# keyboard_main.net
KiCad netlist of a schematic drawn in Altium Designer
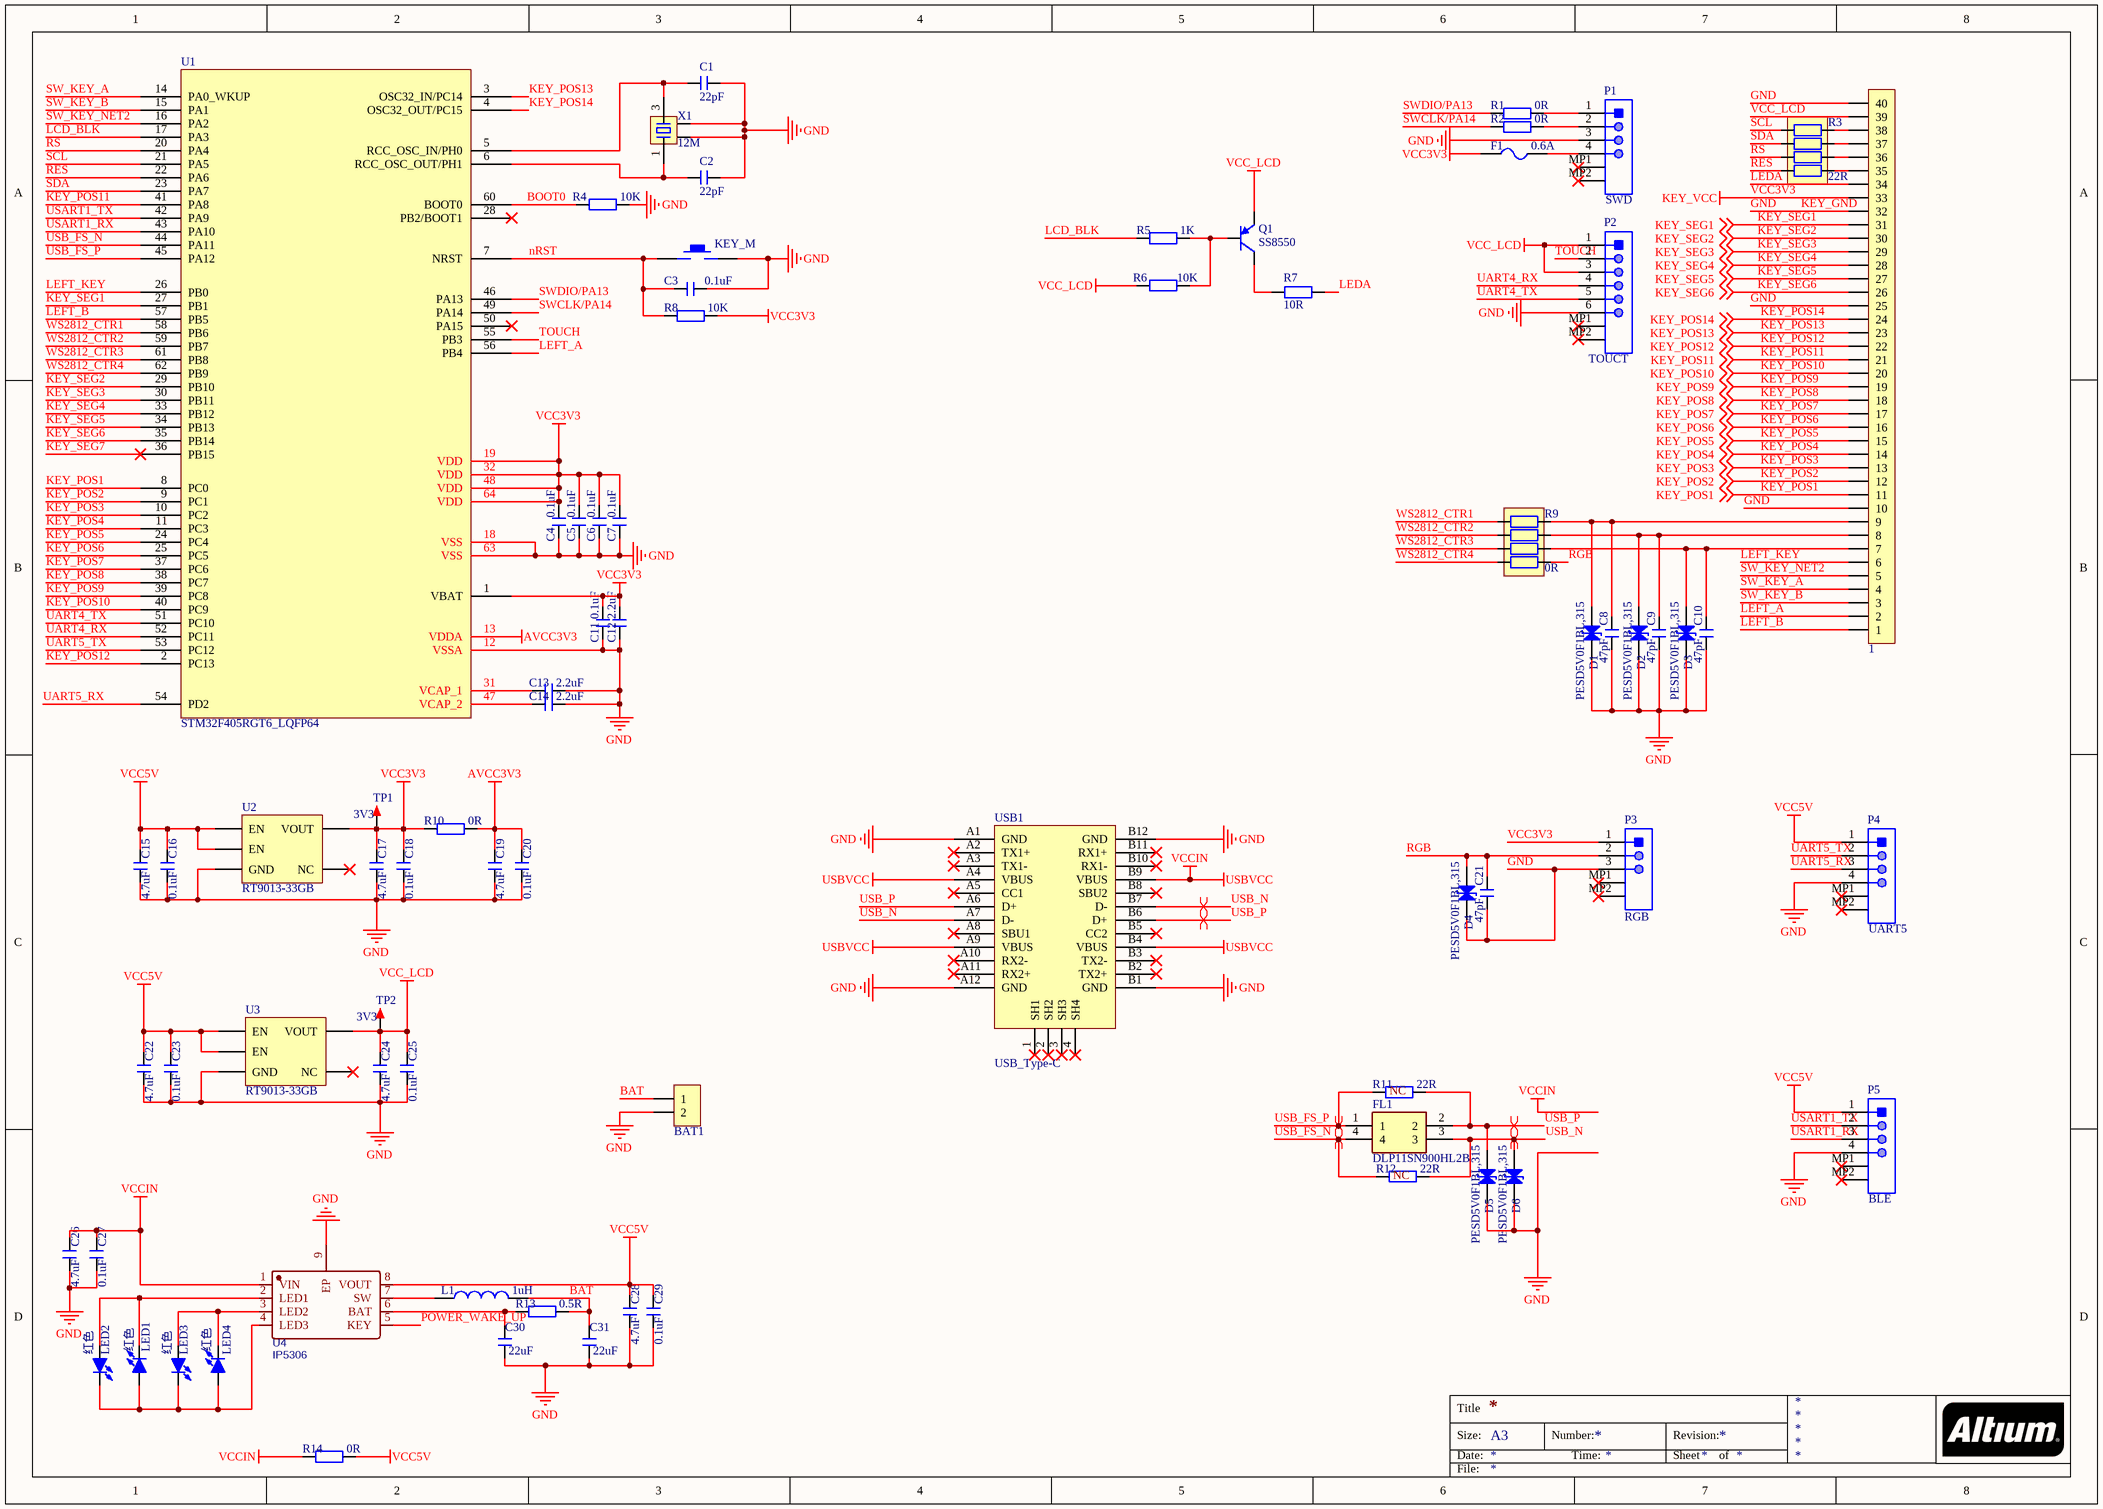
[diagram p0: keyboard_main.SchDoc]

(export (version "E")
  (design (tool "Eeschema 10.0.6"))
  (components
    (comp (ref "1")
      (value "FPC1.0-40P")
      (footprint "FPC0.5 2H-WS-40P")
      (description "FPC连接器")
      (fields (field (name "版权归属") "黎明电子style"))
      (libsource (lib "FPC连接器") (part "FPC-40P"))
    )
    (comp (ref "BAT1")
      (value "HDR-1X2")
      (footprint "XH2.54-WI-2P")
      (description "2P接插件")
      (libsource (lib "5.3 - 接插件-脚距2.54 (100mil) ") (part "Header 2"))
    )
    (comp (ref "C1")
      (value "22pF")
      (footprint "C 0402_L")
      (description "贴片电容")
      (libsource (lib "0.1 - 电阻-电容-电感") (part "C"))
    )
    (comp (ref "C2")
      (value "22pF")
      (footprint "C 0402_L")
      (description "贴片电容")
      (libsource (lib "0.1 - 电阻-电容-电感") (part "C"))
    )
    (comp (ref "C3")
      (value "0.1uF")
      (footprint "C 0402_L")
      (description "贴片电容")
      (libsource (lib "0.1 - 电阻-电容-电感") (part "C"))
    )
    (comp (ref "C4")
      (value "0.1uF")
      (footprint "C 0402_L")
      (description "贴片电容")
      (libsource (lib "0.1 - 电阻-电容-电感") (part "C"))
    )
    (comp (ref "C5")
      (value "0.1uF")
      (footprint "C 0402_L")
      (description "贴片电容")
      (libsource (lib "0.1 - 电阻-电容-电感") (part "C"))
    )
    (comp (ref "C6")
      (value "0.1uF")
      (footprint "C 0402_L")
      (description "贴片电容")
      (libsource (lib "0.1 - 电阻-电容-电感") (part "C"))
    )
    (comp (ref "C7")
      (value "0.1uF")
      (footprint "C 0402_L")
      (description "贴片电容")
      (libsource (lib "0.1 - 电阻-电容-电感") (part "C"))
    )
    (comp (ref "C8")
      (value "47pF")
      (footprint "C 0402_L")
      (description "贴片电容")
      (libsource (lib "0.1 - 电阻-电容-电感") (part "C"))
    )
    (comp (ref "C9")
      (value "47pF")
      (footprint "C 0402_L")
      (description "贴片电容")
      (libsource (lib "0.1 - 电阻-电容-电感") (part "C"))
    )
    (comp (ref "C10")
      (value "47pF")
      (footprint "C 0402_L")
      (description "贴片电容")
      (libsource (lib "0.1 - 电阻-电容-电感") (part "C"))
    )
    (comp (ref "C11")
      (value "0.1uF")
      (footprint "C 0402_L")
      (description "贴片电容")
      (libsource (lib "0.1 - 电阻-电容-电感") (part "C"))
    )
    (comp (ref "C12")
      (value "2.2uF")
      (footprint "C 0402_L")
      (description "贴片电容")
      (libsource (lib "0.1 - 电阻-电容-电感") (part "C"))
    )
    (comp (ref "C13")
      (value "2.2uF")
      (footprint "C 0402_L")
      (description "贴片电容")
      (libsource (lib "0.1 - 电阻-电容-电感") (part "C"))
    )
    (comp (ref "C14")
      (value "2.2uF")
      (footprint "C 0402_L")
      (description "贴片电容")
      (libsource (lib "0.1 - 电阻-电容-电感") (part "C"))
    )
    (comp (ref "C15")
      (value "4.7uF")
      (footprint "C 0402_L")
      (description "贴片电容")
      (libsource (lib "0.1 - 电阻-电容-电感") (part "C"))
    )
    (comp (ref "C16")
      (value "0.1uF")
      (footprint "C 0402_L")
      (description "贴片电容")
      (libsource (lib "0.1 - 电阻-电容-电感") (part "C"))
    )
    (comp (ref "C17")
      (value "4.7uF")
      (footprint "C 0402_L")
      (description "贴片电容")
      (libsource (lib "0.1 - 电阻-电容-电感") (part "C"))
    )
    (comp (ref "C18")
      (value "0.1uF")
      (footprint "C 0402_L")
      (description "贴片电容")
      (libsource (lib "0.1 - 电阻-电容-电感") (part "C"))
    )
    (comp (ref "C19")
      (value "4.7uF")
      (footprint "C 0402_L")
      (description "贴片电容")
      (libsource (lib "0.1 - 电阻-电容-电感") (part "C"))
    )
    (comp (ref "C20")
      (value "0.1uF")
      (footprint "C 0402_L")
      (description "贴片电容")
      (libsource (lib "0.1 - 电阻-电容-电感") (part "C"))
    )
    (comp (ref "C21")
      (value "47pF")
      (footprint "C 0402_L")
      (description "贴片电容")
      (libsource (lib "0.1 - 电阻-电容-电感") (part "C"))
    )
    (comp (ref "C22")
      (value "4.7uF")
      (footprint "C 0402_L")
      (description "贴片电容")
      (libsource (lib "0.1 - 电阻-电容-电感") (part "C"))
    )
    (comp (ref "C23")
      (value "0.1uF")
      (footprint "C 0402_L")
      (description "贴片电容")
      (libsource (lib "0.1 - 电阻-电容-电感") (part "C"))
    )
    (comp (ref "C24")
      (value "4.7uF")
      (footprint "C 0402_L")
      (description "贴片电容")
      (libsource (lib "0.1 - 电阻-电容-电感") (part "C"))
    )
    (comp (ref "C25")
      (value "0.1uF")
      (footprint "C 0402_L")
      (description "贴片电容")
      (libsource (lib "0.1 - 电阻-电容-电感") (part "C"))
    )
    (comp (ref "C26")
      (value "4.7uF")
      (footprint "C 0402_L")
      (description "贴片电容")
      (libsource (lib "0.1 - 电阻-电容-电感") (part "C"))
    )
    (comp (ref "C27")
      (value "0.1uF")
      (footprint "C 0402_L")
      (description "贴片电容")
      (libsource (lib "0.1 - 电阻-电容-电感") (part "C"))
    )
    (comp (ref "C28")
      (value "4.7uF")
      (footprint "C 0402_L")
      (description "贴片电容")
      (libsource (lib "0.1 - 电阻-电容-电感") (part "C"))
    )
    (comp (ref "C29")
      (value "0.1uF")
      (footprint "C 0402_L")
      (description "贴片电容")
      (libsource (lib "0.1 - 电阻-电容-电感") (part "C"))
    )
    (comp (ref "C30")
      (value "22uF")
      (footprint "C 0603_L")
      (description "贴片电容")
      (libsource (lib "0.1 - 电阻-电容-电感") (part "C"))
    )
    (comp (ref "C31")
      (value "22uF")
      (footprint "C 0603_L")
      (description "贴片电容")
      (libsource (lib "0.1 - 电阻-电容-电感") (part "C"))
    )
    (comp (ref "D1")
      (value "PESD5V0F1BL,315")
      (footprint "SOD-882_L1.0-W0.6-BI")
      (description "PESD5V0F1BL,315、ESD二极管、5.5V")
      (libsource (lib "0.2 -  二极管-整流桥") (part "PESD5V0F1BL,315"))
    )
    (comp (ref "D2")
      (value "PESD5V0F1BL,315")
      (footprint "SOD-882_L1.0-W0.6-BI")
      (description "PESD5V0F1BL,315、ESD二极管、5.5V")
      (libsource (lib "0.2 -  二极管-整流桥") (part "PESD5V0F1BL,315"))
    )
    (comp (ref "D3")
      (value "PESD5V0F1BL,315")
      (footprint "SOD-882_L1.0-W0.6-BI")
      (description "PESD5V0F1BL,315、ESD二极管、5.5V")
      (libsource (lib "0.2 -  二极管-整流桥") (part "PESD5V0F1BL,315"))
    )
    (comp (ref "D4")
      (value "PESD5V0F1BL,315")
      (footprint "SOD-882_L1.0-W0.6-BI")
      (description "PESD5V0F1BL,315、ESD二极管、5.5V")
      (libsource (lib "0.2 -  二极管-整流桥") (part "PESD5V0F1BL,315"))
    )
    (comp (ref "D5")
      (value "PESD5V0F1BL,315")
      (footprint "SOD-882_L1.0-W0.6-BI")
      (description "PESD5V0F1BL,315、ESD二极管、5.5V")
      (libsource (lib "0.2 -  二极管-整流桥") (part "PESD5V0F1BL,315"))
    )
    (comp (ref "D6")
      (value "PESD5V0F1BL,315")
      (footprint "SOD-882_L1.0-W0.6-BI")
      (description "PESD5V0F1BL,315、ESD二极管、5.5V")
      (libsource (lib "0.2 -  二极管-整流桥") (part "PESD5V0F1BL,315"))
    )
    (comp (ref "F1")
      (value "0.6A")
      (footprint "FU 0402")
      (description "贴片保险丝")
      (libsource (lib "2.0 - 保险丝-晶振-光耦") (part "FU"))
    )
    (comp (ref "FL1")
      (value "DLP11SN900HL2B")
      (footprint "vSeasky:DLP11SA350HL2B")
      (description "Filter")
      (fields (field (name "MOUSER PART NUMBER") "81-DLP11SN900HL2B"))
      (libsource (lib "vSeasky") (part "DLP11SN900HL2B"))
    )
    (comp (ref "L1")
      (value "1uH")
      (footprint "L 1812")
      (description "小功率贴片电感")
      (libsource (lib "0.1 - 电阻-电容-电感") (part "L"))
    )
    (comp (ref "LED1")
      (value "红色")
      (footprint "LED 0805G")
      (description "贴片LED")
      (libsource (lib "0.3 - LED发光二极管") (part "LED-SMD"))
    )
    (comp (ref "LED2")
      (value "红色")
      (footprint "LED 0805G")
      (description "贴片LED")
      (libsource (lib "0.3 - LED发光二极管") (part "LED-SMD"))
    )
    (comp (ref "LED3")
      (value "红色")
      (footprint "LED 0805G")
      (description "贴片LED")
      (libsource (lib "0.3 - LED发光二极管") (part "LED-SMD"))
    )
    (comp (ref "LED4")
      (value "红色")
      (footprint "LED 0805G")
      (description "贴片LED")
      (libsource (lib "0.3 - LED发光二极管") (part "LED-SMD"))
    )
    (comp (ref "P1")
      (value "SWD")
      (footprint "JST-SM04B-GHS-TB_V")
      (fields (field (name "MANUFACTURER") "JST"))
      (libsource (lib "JST GH connector") (part "SM04B-GHS-TB(LF)(SN)"))
    )
    (comp (ref "P2")
      (value "TOUCT")
      (footprint "JST-SM06B-GHS-TB_V")
      (fields (field (name "MANUFACTURER") "JST"))
      (libsource (lib "JST GH connector") (part "SM06B-GHS-TB(LF)(SN)"))
    )
    (comp (ref "P3")
      (value "RGB")
      (footprint "JST-SM03B-GHS-TB_V")
      (fields (field (name "MANUFACTURER") "JST"))
      (libsource (lib "JST GH connector") (part "SM03B-GHS-TB(LF)(SN)"))
    )
    (comp (ref "P4")
      (value "UART5")
      (footprint "JST-SM04B-GHS-TB_V")
      (fields (field (name "MANUFACTURER") "JST"))
      (libsource (lib "JST GH connector") (part "SM04B-GHS-TB(LF)(SN)"))
    )
    (comp (ref "P5")
      (value "BLE")
      (footprint "JST-SM04B-GHS-TB_V")
      (fields (field (name "MANUFACTURER") "JST"))
      (libsource (lib "JST GH connector") (part "SM04B-GHS-TB(LF)(SN)"))
    )
    (comp (ref "Q1")
      (value "SS8550")
      (footprint "SOT23-3N")
      (description "高频放大-PNP型")
      (libsource (lib "0.4 - 三极管") (part "8550-SMD"))
    )
    (comp (ref "R1")
      (value "0R")
      (footprint "R 0402_L")
      (description "贴片电阻")
      (libsource (lib "0.1 - 电阻-电容-电感") (part "R"))
    )
    (comp (ref "R2")
      (value "0R")
      (footprint "R 0402_L")
      (description "贴片电阻")
      (libsource (lib "0.1 - 电阻-电容-电感") (part "R"))
    )
    (comp (ref "R3")
      (value "22R")
      (footprint "RCA-8P4R-0402")
      (description "贴片排阻")
      (libsource (lib "0.1 - 电阻-电容-电感") (part "R-8P4R"))
    )
    (comp (ref "R4")
      (value "10K")
      (footprint "R 0402_L")
      (description "贴片电阻")
      (libsource (lib "0.1 - 电阻-电容-电感") (part "R"))
    )
    (comp (ref "R5")
      (value "1K")
      (footprint "R 0402_L")
      (description "贴片电阻")
      (libsource (lib "0.1 - 电阻-电容-电感") (part "R"))
    )
    (comp (ref "R6")
      (value "10K")
      (footprint "R 0402_L")
      (description "贴片电阻")
      (libsource (lib "0.1 - 电阻-电容-电感") (part "R"))
    )
    (comp (ref "R7")
      (value "10R")
      (footprint "R 0402_L")
      (description "贴片电阻")
      (libsource (lib "0.1 - 电阻-电容-电感") (part "R"))
    )
    (comp (ref "R8")
      (value "10K")
      (footprint "R 0402_L")
      (description "贴片电阻")
      (libsource (lib "0.1 - 电阻-电容-电感") (part "R"))
    )
    (comp (ref "R9")
      (value "0R")
      (footprint "RCA-8P4R-0402")
      (description "贴片排阻")
      (libsource (lib "0.1 - 电阻-电容-电感") (part "R-8P4R"))
    )
    (comp (ref "R10")
      (value "0R")
      (footprint "R 0402_L")
      (description "贴片电阻")
      (libsource (lib "0.1 - 电阻-电容-电感") (part "R"))
    )
    (comp (ref "R11")
      (value "22R")
      (footprint "R 0402_L")
      (description "贴片电阻")
      (libsource (lib "0.1 - 电阻-电容-电感") (part "R"))
    )
    (comp (ref "R12")
      (value "22R")
      (footprint "R 0402_L")
      (description "贴片电阻")
      (libsource (lib "0.1 - 电阻-电容-电感") (part "R"))
    )
    (comp (ref "R13")
      (value "0.5R")
      (footprint "R 0603_L")
      (description "贴片电阻")
      (libsource (lib "0.1 - 电阻-电容-电感") (part "R"))
    )
    (comp (ref "R14")
      (value "0R")
      (footprint "R 0805_L")
      (description "贴片电阻")
      (libsource (lib "0.1 - 电阻-电容-电感") (part "R"))
    )
    (comp (ref "RST1")
      (value "KEY_M")
      (footprint "SMD-3.2*4.2")
      (libsource (lib "mx_pcb_library") (part "KEY_M"))
    )
    (comp (ref "TP1")
      (value "3V3")
      (footprint "TEST 1")
      (description "测试点")
      (libsource (lib "4.1 - 未分类器件") (part "TEST"))
    )
    (comp (ref "TP2")
      (value "3V3")
      (footprint "TEST 1")
      (description "测试点")
      (libsource (lib "4.1 - 未分类器件") (part "TEST"))
    )
    (comp (ref "U1")
      (value "STM32F405RGT6_LQFP64")
      (footprint "LQFP-64_10X10X05P")
      (libsource (lib "mx_pcb_library") (part "STM32F405RGT6_LQFP64"))
    )
    (comp (ref "U2")
      (value "RT9013-33GB")
      (footprint "SOT23-5M")
      (libsource (lib "mx_pcb_library") (part "RT9013-33GB"))
    )
    (comp (ref "U3")
      (value "RT9013-33GB")
      (footprint "SOT23-5M")
      (libsource (lib "mx_pcb_library") (part "RT9013-33GB"))
    )
    (comp (ref "U4")
      (value "IP5306")
      (footprint "SOP-8_EP_150mil")
      (fields (field (name "BOM_SUPPLIER PART") "C181692") (field (name "CONTRIBUTOR") "LCSC"))
      (libsource (lib "mx_pcb_library") (part "IP5306"))
    )
    (comp (ref "USB1")
      (value "USB_Type-C")
      (footprint "Type-C-TOP")
      (libsource (lib "mx_pcb_library") (part "USB_Type-C"))
    )
    (comp (ref "X1")
      (value "12M")
      (footprint "OSC 3225-4P")
      (description "4脚无源晶振")
      (libsource (lib "2.0 - 保险丝-晶振-光耦") (part "XTAL-4P"))
    )
  )
  (nets
    (net (code "1") (name "/BAT") (class "Default")
      (node (ref "BAT1") (pin "1") (pinfunction "1_1") (pintype "passive"))
      (node (ref "C31") (pin "1") (pinfunction "1_1") (pintype "passive"))
      (node (ref "L1") (pin "2") (pinfunction "2_2") (pintype "passive"))
      (node (ref "R13") (pin "2") (pinfunction "2_2") (pintype "passive"))
    )
    (net (code "2") (name "/BOOT0") (class "Default")
      (node (ref "R4") (pin "1") (pinfunction "1_1") (pintype "passive"))
      (node (ref "U1") (pin "60") (pinfunction "BOOT0_60") (pintype "passive"))
    )
    (net (code "3") (name "/KEY_SEG7") (class "Default")
      (node (ref "U1") (pin "36") (pinfunction "PB15_36") (pintype "passive+no_connect"))
    )
    (net (code "4") (name "/LCD_BLK") (class "Default")
      (node (ref "R5") (pin "1") (pinfunction "1_1") (pintype "passive"))
      (node (ref "U1") (pin "17") (pinfunction "PA3_17") (pintype "passive"))
    )
    (net (code "5") (name "/LEDA") (class "Default")
      (node (ref "1") (pin "34") (pinfunction "34_34") (pintype "passive"))
      (node (ref "R7") (pin "1") (pinfunction "1_1") (pintype "passive"))
    )
    (net (code "6") (name "/LEFT_A") (class "Default")
      (node (ref "1") (pin "2") (pinfunction "2_2") (pintype "passive"))
      (node (ref "U1") (pin "56") (pinfunction "PB4_56") (pintype "passive"))
    )
    (net (code "7") (name "/LEFT_B") (class "Default")
      (node (ref "1") (pin "1") (pinfunction "1_1") (pintype "passive"))
      (node (ref "U1") (pin "57") (pinfunction "PB5_57") (pintype "passive"))
    )
    (net (code "8") (name "/LEFT_KEY") (class "Default")
      (node (ref "1") (pin "6") (pinfunction "6_6") (pintype "passive"))
      (node (ref "U1") (pin "26") (pinfunction "PB0_26") (pintype "passive"))
    )
    (net (code "9") (name "/POWER_WAKE_UP") (class "Default")
      (node (ref "U4") (pin "5") (pinfunction "KEY_5") (pintype "passive"))
    )
    (net (code "10") (name "/RES") (class "Default")
      (node (ref "R3") (pin "4") (pinfunction "4_4") (pintype "passive"))
      (node (ref "U1") (pin "22") (pinfunction "PA6_22") (pintype "passive"))
    )
    (net (code "11") (name "/RGB") (class "Default")
      (node (ref "C21") (pin "2") (pinfunction "2_2") (pintype "passive"))
      (node (ref "D4") (pin "1") (pinfunction "A_1") (pintype "passive"))
      (node (ref "P3") (pin "2") (pinfunction "2_2") (pintype "passive"))
      (node (ref "R9") (pin "5") (pinfunction "5_5") (pintype "passive"))
    )
    (net (code "12") (name "/RS") (class "Default")
      (node (ref "R3") (pin "3") (pinfunction "3_3") (pintype "passive"))
      (node (ref "U1") (pin "20") (pinfunction "PA4_20") (pintype "passive"))
    )
    (net (code "13") (name "/SCL") (class "Default")
      (node (ref "R3") (pin "1") (pinfunction "1_1") (pintype "passive"))
      (node (ref "U1") (pin "21") (pinfunction "PA5_21") (pintype "passive"))
    )
    (net (code "14") (name "/SDA") (class "Default")
      (node (ref "R3") (pin "2") (pinfunction "2_2") (pintype "passive"))
      (node (ref "U1") (pin "23") (pinfunction "PA7_23") (pintype "passive"))
    )
    (net (code "15") (name "/SWCLK{slash}PA14") (class "Default")
      (node (ref "R2") (pin "1") (pinfunction "1_1") (pintype "passive"))
      (node (ref "U1") (pin "49") (pinfunction "PA14_49") (pintype "passive"))
    )
    (net (code "16") (name "/SWDIO{slash}PA13") (class "Default")
      (node (ref "R1") (pin "1") (pinfunction "1_1") (pintype "passive"))
      (node (ref "U1") (pin "46") (pinfunction "PA13_46") (pintype "passive"))
    )
    (net (code "17") (name "/SW_KEY_A") (class "Default")
      (node (ref "1") (pin "4") (pinfunction "4_4") (pintype "passive"))
      (node (ref "U1") (pin "14") (pinfunction "PA0_WKUP_14") (pintype "passive"))
    )
    (net (code "18") (name "/SW_KEY_B") (class "Default")
      (node (ref "1") (pin "3") (pinfunction "3_3") (pintype "passive"))
      (node (ref "U1") (pin "15") (pinfunction "PA1_15") (pintype "passive"))
    )
    (net (code "19") (name "/SW_KEY_NET2") (class "Default")
      (node (ref "1") (pin "5") (pinfunction "5_5") (pintype "passive"))
      (node (ref "U1") (pin "16") (pinfunction "PA2_16") (pintype "passive"))
    )
    (net (code "20") (name "/TOUCH") (class "Default")
      (node (ref "P2") (pin "2") (pinfunction "2_2") (pintype "passive"))
      (node (ref "U1") (pin "55") (pinfunction "PB3_55") (pintype "passive"))
    )
    (net (code "21") (name "/UART4_RX") (class "Default")
      (node (ref "P2") (pin "4") (pinfunction "4_4") (pintype "passive"))
      (node (ref "U1") (pin "52") (pinfunction "PC11_52") (pintype "passive"))
    )
    (net (code "22") (name "/UART4_TX") (class "Default")
      (node (ref "P2") (pin "5") (pinfunction "5_5") (pintype "passive"))
      (node (ref "U1") (pin "51") (pinfunction "PC10_51") (pintype "passive"))
    )
    (net (code "23") (name "/UART5_RX") (class "Default")
      (node (ref "P4") (pin "3") (pinfunction "3_3") (pintype "passive"))
      (node (ref "U1") (pin "54") (pinfunction "PD2_54") (pintype "passive"))
    )
    (net (code "24") (name "/UART5_TX") (class "Default")
      (node (ref "P4") (pin "2") (pinfunction "2_2") (pintype "passive"))
      (node (ref "U1") (pin "53") (pinfunction "PC12_53") (pintype "passive"))
    )
    (net (code "25") (name "/USART1_RX") (class "Default")
      (node (ref "P5") (pin "3") (pinfunction "3_3") (pintype "passive"))
      (node (ref "U1") (pin "43") (pinfunction "PA10_43") (pintype "passive"))
    )
    (net (code "26") (name "/USART1_TX") (class "Default")
      (node (ref "P5") (pin "2") (pinfunction "2_2") (pintype "passive"))
      (node (ref "U1") (pin "42") (pinfunction "PA9_42") (pintype "passive"))
    )
    (net (code "27") (name "/USB_FS_N") (class "Default")
      (node (ref "FL1") (pin "4") (pinfunction "4_4") (pintype "passive"))
      (node (ref "R12") (pin "1") (pinfunction "1_1") (pintype "passive"))
      (node (ref "U1") (pin "44") (pinfunction "PA11_44") (pintype "passive"))
    )
    (net (code "28") (name "/USB_FS_P") (class "Default")
      (node (ref "FL1") (pin "1") (pinfunction "1_1") (pintype "passive"))
      (node (ref "R11") (pin "1") (pinfunction "1_1") (pintype "passive"))
      (node (ref "U1") (pin "45") (pinfunction "PA12_45") (pintype "passive"))
    )
    (net (code "29") (name "/USB_N") (class "Default")
      (node (ref "D6") (pin "1") (pinfunction "A_1") (pintype "passive"))
      (node (ref "FL1") (pin "3") (pinfunction "3_3") (pintype "passive"))
      (node (ref "R12") (pin "2") (pinfunction "2_2") (pintype "passive"))
      (node (ref "USB1") (pin "A7") (pinfunction "D-_A7") (pintype "passive"))
      (node (ref "USB1") (pin "B7") (pinfunction "D-_B7") (pintype "passive"))
    )
    (net (code "30") (name "/USB_P") (class "Default")
      (node (ref "D5") (pin "1") (pinfunction "A_1") (pintype "passive"))
      (node (ref "FL1") (pin "2") (pinfunction "2_2") (pintype "passive"))
      (node (ref "R11") (pin "2") (pinfunction "2_2") (pintype "passive"))
      (node (ref "USB1") (pin "A6") (pinfunction "D+_A6") (pintype "passive"))
      (node (ref "USB1") (pin "B6") (pinfunction "D+_B6") (pintype "passive"))
    )
    (net (code "31") (name "/WS2812_CTR1") (class "Default")
      (node (ref "R9") (pin "1") (pinfunction "1_1") (pintype "passive"))
      (node (ref "U1") (pin "58") (pinfunction "PB6_58") (pintype "passive"))
    )
    (net (code "32") (name "/WS2812_CTR2") (class "Default")
      (node (ref "R9") (pin "2") (pinfunction "2_2") (pintype "passive"))
      (node (ref "U1") (pin "59") (pinfunction "PB7_59") (pintype "passive"))
    )
    (net (code "33") (name "/WS2812_CTR3") (class "Default")
      (node (ref "R9") (pin "3") (pinfunction "3_3") (pintype "passive"))
      (node (ref "U1") (pin "61") (pinfunction "PB8_61") (pintype "passive"))
    )
    (net (code "34") (name "/WS2812_CTR4") (class "Default")
      (node (ref "R9") (pin "4") (pinfunction "4_4") (pintype "passive"))
      (node (ref "U1") (pin "62") (pinfunction "PB9_62") (pintype "passive"))
    )
    (net (code "35") (name "/nRST") (class "Default")
      (node (ref "C3") (pin "1") (pinfunction "1_1") (pintype "passive"))
      (node (ref "R8") (pin "1") (pinfunction "1_1") (pintype "passive"))
      (node (ref "RST1") (pin "1") (pinfunction "1_1") (pintype "passive"))
      (node (ref "U1") (pin "7") (pinfunction "NRST_7") (pintype "passive"))
    )
    (net (code "36") (name "AVCC3V3") (class "Default")
      (node (ref "C19") (pin "1") (pinfunction "1_1") (pintype "passive"))
      (node (ref "C20") (pin "1") (pinfunction "1_1") (pintype "passive"))
      (node (ref "R10") (pin "2") (pinfunction "2_2") (pintype "passive"))
      (node (ref "U1") (pin "13") (pinfunction "VDDA_13") (pintype "passive"))
    )
    (net (code "37") (name "GND") (class "Default")
      (node (ref "1") (pin "10") (pinfunction "10_10") (pintype "passive"))
      (node (ref "1") (pin "25") (pinfunction "25_25") (pintype "passive"))
      (node (ref "1") (pin "32") (pinfunction "32_32") (pintype "passive"))
      (node (ref "1") (pin "40") (pinfunction "40_40") (pintype "passive"))
      (node (ref "BAT1") (pin "2") (pinfunction "2_2") (pintype "passive"))
      (node (ref "C1") (pin "2") (pinfunction "2_2") (pintype "passive"))
      (node (ref "C10") (pin "1") (pinfunction "1_1") (pintype "passive"))
      (node (ref "C11") (pin "1") (pinfunction "1_1") (pintype "passive"))
      (node (ref "C12") (pin "1") (pinfunction "1_1") (pintype "passive"))
      (node (ref "C13") (pin "1") (pinfunction "1_1") (pintype "passive"))
      (node (ref "C14") (pin "1") (pinfunction "1_1") (pintype "passive"))
      (node (ref "C15") (pin "2") (pinfunction "2_2") (pintype "passive"))
      (node (ref "C16") (pin "2") (pinfunction "2_2") (pintype "passive"))
      (node (ref "C17") (pin "2") (pinfunction "2_2") (pintype "passive"))
      (node (ref "C18") (pin "2") (pinfunction "2_2") (pintype "passive"))
      (node (ref "C19") (pin "2") (pinfunction "2_2") (pintype "passive"))
      (node (ref "C2") (pin "2") (pinfunction "2_2") (pintype "passive"))
      (node (ref "C20") (pin "2") (pinfunction "2_2") (pintype "passive"))
      (node (ref "C21") (pin "1") (pinfunction "1_1") (pintype "passive"))
      (node (ref "C22") (pin "2") (pinfunction "2_2") (pintype "passive"))
      (node (ref "C23") (pin "2") (pinfunction "2_2") (pintype "passive"))
      (node (ref "C24") (pin "2") (pinfunction "2_2") (pintype "passive"))
      (node (ref "C25") (pin "2") (pinfunction "2_2") (pintype "passive"))
      (node (ref "C26") (pin "2") (pinfunction "2_2") (pintype "passive"))
      (node (ref "C27") (pin "2") (pinfunction "2_2") (pintype "passive"))
      (node (ref "C28") (pin "2") (pinfunction "2_2") (pintype "passive"))
      (node (ref "C29") (pin "2") (pinfunction "2_2") (pintype "passive"))
      (node (ref "C3") (pin "2") (pinfunction "2_2") (pintype "passive"))
      (node (ref "C30") (pin "1") (pinfunction "1_1") (pintype "passive"))
      (node (ref "C31") (pin "2") (pinfunction "2_2") (pintype "passive"))
      (node (ref "C4") (pin "1") (pinfunction "1_1") (pintype "passive"))
      (node (ref "C5") (pin "1") (pinfunction "1_1") (pintype "passive"))
      (node (ref "C6") (pin "1") (pinfunction "1_1") (pintype "passive"))
      (node (ref "C7") (pin "1") (pinfunction "1_1") (pintype "passive"))
      (node (ref "C8") (pin "1") (pinfunction "1_1") (pintype "passive"))
      (node (ref "C9") (pin "1") (pinfunction "1_1") (pintype "passive"))
      (node (ref "D1") (pin "2") (pinfunction "K_2") (pintype "passive"))
      (node (ref "D2") (pin "2") (pinfunction "K_2") (pintype "passive"))
      (node (ref "D3") (pin "2") (pinfunction "K_2") (pintype "passive"))
      (node (ref "D4") (pin "2") (pinfunction "K_2") (pintype "passive"))
      (node (ref "D5") (pin "2") (pinfunction "K_2") (pintype "passive"))
      (node (ref "D6") (pin "2") (pinfunction "K_2") (pintype "passive"))
      (node (ref "P1") (pin "3") (pinfunction "3_3") (pintype "passive"))
      (node (ref "P2") (pin "6") (pinfunction "6_6") (pintype "passive"))
      (node (ref "P3") (pin "3") (pinfunction "3_3") (pintype "passive"))
      (node (ref "P4") (pin "4") (pinfunction "4_4") (pintype "passive"))
      (node (ref "P5") (pin "4") (pinfunction "4_4") (pintype "passive"))
      (node (ref "R4") (pin "2") (pinfunction "2_2") (pintype "passive"))
      (node (ref "RST1") (pin "2") (pinfunction "2_2") (pintype "passive"))
      (node (ref "U1") (pin "12") (pinfunction "VSSA_12") (pintype "passive"))
      (node (ref "U1") (pin "18") (pinfunction "VSS_18") (pintype "passive"))
      (node (ref "U1") (pin "63") (pinfunction "VSS_63") (pintype "passive"))
      (node (ref "U2") (pin "2") (pinfunction "GND_2") (pintype "passive"))
      (node (ref "U3") (pin "2") (pinfunction "GND_2") (pintype "passive"))
      (node (ref "U4") (pin "9") (pinfunction "EP_9") (pintype "passive"))
      (node (ref "USB1") (pin "A1") (pinfunction "GND_A1") (pintype "passive"))
      (node (ref "USB1") (pin "A12") (pinfunction "GND_A12") (pintype "passive"))
      (node (ref "USB1") (pin "B1") (pinfunction "GND_B1") (pintype "passive"))
      (node (ref "USB1") (pin "B12") (pinfunction "GND_B12") (pintype "passive"))
      (node (ref "X1") (pin "2") (pinfunction "2_2") (pintype "passive"))
      (node (ref "X1") (pin "4") (pinfunction "4_4") (pintype "passive"))
    )
    (net (code "38") (name "KEY_POS1") (class "Default")
      (node (ref "1") (pin "11") (pinfunction "11_11") (pintype "passive"))
      (node (ref "U1") (pin "8") (pinfunction "PC0_8") (pintype "passive"))
    )
    (net (code "39") (name "KEY_POS2") (class "Default")
      (node (ref "1") (pin "12") (pinfunction "12_12") (pintype "passive"))
      (node (ref "U1") (pin "9") (pinfunction "PC1_9") (pintype "passive"))
    )
    (net (code "40") (name "KEY_POS3") (class "Default")
      (node (ref "1") (pin "13") (pinfunction "13_13") (pintype "passive"))
      (node (ref "U1") (pin "10") (pinfunction "PC2_10") (pintype "passive"))
    )
    (net (code "41") (name "KEY_POS4") (class "Default")
      (node (ref "1") (pin "14") (pinfunction "14_14") (pintype "passive"))
      (node (ref "U1") (pin "11") (pinfunction "PC3_11") (pintype "passive"))
    )
    (net (code "42") (name "KEY_POS5") (class "Default")
      (node (ref "1") (pin "15") (pinfunction "15_15") (pintype "passive"))
      (node (ref "U1") (pin "24") (pinfunction "PC4_24") (pintype "passive"))
    )
    (net (code "43") (name "KEY_POS6") (class "Default")
      (node (ref "1") (pin "16") (pinfunction "16_16") (pintype "passive"))
      (node (ref "U1") (pin "25") (pinfunction "PC5_25") (pintype "passive"))
    )
    (net (code "44") (name "KEY_POS7") (class "Default")
      (node (ref "1") (pin "17") (pinfunction "17_17") (pintype "passive"))
      (node (ref "U1") (pin "37") (pinfunction "PC6_37") (pintype "passive"))
    )
    (net (code "45") (name "KEY_POS8") (class "Default")
      (node (ref "1") (pin "18") (pinfunction "18_18") (pintype "passive"))
      (node (ref "U1") (pin "38") (pinfunction "PC7_38") (pintype "passive"))
    )
    (net (code "46") (name "KEY_POS9") (class "Default")
      (node (ref "1") (pin "19") (pinfunction "19_19") (pintype "passive"))
      (node (ref "U1") (pin "39") (pinfunction "PC8_39") (pintype "passive"))
    )
    (net (code "47") (name "KEY_POS10") (class "Default")
      (node (ref "1") (pin "20") (pinfunction "20_20") (pintype "passive"))
      (node (ref "U1") (pin "40") (pinfunction "PC9_40") (pintype "passive"))
    )
    (net (code "48") (name "KEY_POS11") (class "Default")
      (node (ref "1") (pin "21") (pinfunction "21_21") (pintype "passive"))
      (node (ref "U1") (pin "41") (pinfunction "PA8_41") (pintype "passive"))
    )
    (net (code "49") (name "KEY_POS12") (class "Default")
      (node (ref "1") (pin "22") (pinfunction "22_22") (pintype "passive"))
      (node (ref "U1") (pin "2") (pinfunction "PC13_2") (pintype "passive"))
    )
    (net (code "50") (name "KEY_POS13") (class "Default")
      (node (ref "1") (pin "23") (pinfunction "23_23") (pintype "passive"))
      (node (ref "U1") (pin "3") (pinfunction "OSC32_IN/PC14_3") (pintype "passive"))
    )
    (net (code "51") (name "KEY_POS14") (class "Default")
      (node (ref "1") (pin "24") (pinfunction "24_24") (pintype "passive"))
      (node (ref "U1") (pin "4") (pinfunction "OSC32_OUT/PC15_4") (pintype "passive"))
    )
    (net (code "52") (name "KEY_SEG1") (class "Default")
      (node (ref "1") (pin "31") (pinfunction "31_31") (pintype "passive"))
      (node (ref "U1") (pin "27") (pinfunction "PB1_27") (pintype "passive"))
    )
    (net (code "53") (name "KEY_SEG2") (class "Default")
      (node (ref "1") (pin "30") (pinfunction "30_30") (pintype "passive"))
      (node (ref "U1") (pin "29") (pinfunction "PB10_29") (pintype "passive"))
    )
    (net (code "54") (name "KEY_SEG3") (class "Default")
      (node (ref "1") (pin "29") (pinfunction "29_29") (pintype "passive"))
      (node (ref "U1") (pin "30") (pinfunction "PB11_30") (pintype "passive"))
    )
    (net (code "55") (name "KEY_SEG4") (class "Default")
      (node (ref "1") (pin "28") (pinfunction "28_28") (pintype "passive"))
      (node (ref "U1") (pin "33") (pinfunction "PB12_33") (pintype "passive"))
    )
    (net (code "56") (name "KEY_SEG5") (class "Default")
      (node (ref "1") (pin "27") (pinfunction "27_27") (pintype "passive"))
      (node (ref "U1") (pin "34") (pinfunction "PB13_34") (pintype "passive"))
    )
    (net (code "57") (name "KEY_SEG6") (class "Default")
      (node (ref "1") (pin "26") (pinfunction "26_26") (pintype "passive"))
      (node (ref "U1") (pin "35") (pinfunction "PB14_35") (pintype "passive"))
    )
    (net (code "58") (name "KEY_VCC") (class "Default")
      (node (ref "1") (pin "33") (pinfunction "33_33") (pintype "passive"))
      (node (ref "C11") (pin "2") (pinfunction "2_2") (pintype "passive"))
      (node (ref "C12") (pin "2") (pinfunction "2_2") (pintype "passive"))
      (node (ref "C17") (pin "1") (pinfunction "1_1") (pintype "passive"))
      (node (ref "C18") (pin "1") (pinfunction "1_1") (pintype "passive"))
      (node (ref "C4") (pin "2") (pinfunction "2_2") (pintype "passive"))
      (node (ref "C5") (pin "2") (pinfunction "2_2") (pintype "passive"))
      (node (ref "C6") (pin "2") (pinfunction "2_2") (pintype "passive"))
      (node (ref "C7") (pin "2") (pinfunction "2_2") (pintype "passive"))
      (node (ref "F1") (pin "1") (pinfunction "1_1") (pintype "passive"))
      (node (ref "P3") (pin "1") (pinfunction "1_1") (pintype "passive"))
      (node (ref "R10") (pin "1") (pinfunction "1_1") (pintype "passive"))
      (node (ref "R8") (pin "2") (pinfunction "2_2") (pintype "passive"))
      (node (ref "TP1") (pin "1") (pinfunction "1_1") (pintype "passive"))
      (node (ref "U1") (pin "1") (pinfunction "VBAT_1") (pintype "passive"))
      (node (ref "U1") (pin "19") (pinfunction "VDD_19") (pintype "passive"))
      (node (ref "U1") (pin "32") (pinfunction "VDD_32") (pintype "passive"))
      (node (ref "U1") (pin "48") (pinfunction "VDD_48") (pintype "passive"))
      (node (ref "U1") (pin "64") (pinfunction "VDD_64") (pintype "passive"))
      (node (ref "U2") (pin "5") (pinfunction "VOUT_5") (pintype "passive"))
    )
    (net (code "59") (name "Net-(1-Pad35)") (class "Default")
      (node (ref "1") (pin "35") (pinfunction "35_35") (pintype "passive"))
      (node (ref "R3") (pin "5") (pinfunction "5_5") (pintype "passive"))
    )
    (net (code "60") (name "Net-(1-Pad36)") (class "Default")
      (node (ref "1") (pin "36") (pinfunction "36_36") (pintype "passive"))
      (node (ref "R3") (pin "6") (pinfunction "6_6") (pintype "passive"))
    )
    (net (code "61") (name "Net-(1-Pad37)") (class "Default")
      (node (ref "1") (pin "37") (pinfunction "37_37") (pintype "passive"))
      (node (ref "R3") (pin "7") (pinfunction "7_7") (pintype "passive"))
    )
    (net (code "62") (name "Net-(1-Pad38)") (class "Default")
      (node (ref "1") (pin "38") (pinfunction "38_38") (pintype "passive"))
      (node (ref "R3") (pin "8") (pinfunction "8_8") (pintype "passive"))
    )
    (net (code "63") (name "Net-(D1-A)") (class "Default")
      (node (ref "1") (pin "9") (pinfunction "9_9") (pintype "passive"))
      (node (ref "C8") (pin "2") (pinfunction "2_2") (pintype "passive"))
      (node (ref "D1") (pin "1") (pinfunction "A_1") (pintype "passive"))
      (node (ref "R9") (pin "8") (pinfunction "8_8") (pintype "passive"))
    )
    (net (code "64") (name "Net-(D2-A)") (class "Default")
      (node (ref "1") (pin "8") (pinfunction "8_8") (pintype "passive"))
      (node (ref "C9") (pin "2") (pinfunction "2_2") (pintype "passive"))
      (node (ref "D2") (pin "1") (pinfunction "A_1") (pintype "passive"))
      (node (ref "R9") (pin "7") (pinfunction "7_7") (pintype "passive"))
    )
    (net (code "65") (name "Net-(D3-A)") (class "Default")
      (node (ref "1") (pin "7") (pinfunction "7_7") (pintype "passive"))
      (node (ref "C10") (pin "2") (pinfunction "2_2") (pintype "passive"))
      (node (ref "D3") (pin "1") (pinfunction "A_1") (pintype "passive"))
      (node (ref "R9") (pin "6") (pinfunction "6_6") (pintype "passive"))
    )
    (net (code "66") (name "Net-(F1-Pad2)") (class "Default")
      (node (ref "F1") (pin "2") (pinfunction "2_2") (pintype "passive"))
      (node (ref "P1") (pin "4") (pinfunction "4_4") (pintype "passive"))
    )
    (net (code "67") (name "Net-(LED1-A)") (class "Default")
      (node (ref "LED1") (pin "1") (pinfunction "A_1") (pintype "passive"))
      (node (ref "LED2") (pin "2") (pinfunction "K_2") (pintype "passive"))
      (node (ref "LED3") (pin "2") (pinfunction "K_2") (pintype "passive"))
      (node (ref "LED4") (pin "1") (pinfunction "A_1") (pintype "passive"))
      (node (ref "U4") (pin "4") (pinfunction "LED3_4") (pintype "passive"))
    )
    (net (code "68") (name "Net-(LED1-K)") (class "Default")
      (node (ref "LED1") (pin "2") (pinfunction "K_2") (pintype "passive"))
      (node (ref "LED2") (pin "1") (pinfunction "A_1") (pintype "passive"))
      (node (ref "U4") (pin "2") (pinfunction "LED1_2") (pintype "passive"))
    )
    (net (code "69") (name "Net-(LED3-A)") (class "Default")
      (node (ref "LED3") (pin "1") (pinfunction "A_1") (pintype "passive"))
      (node (ref "LED4") (pin "2") (pinfunction "K_2") (pintype "passive"))
      (node (ref "U4") (pin "3") (pinfunction "LED2_3") (pintype "passive"))
    )
    (net (code "70") (name "Net-(P1-Pad1)") (class "Default")
      (node (ref "P1") (pin "1") (pinfunction "1_1") (pintype "passive"))
      (node (ref "R1") (pin "2") (pinfunction "2_2") (pintype "passive"))
    )
    (net (code "71") (name "Net-(P1-Pad2)") (class "Default")
      (node (ref "P1") (pin "2") (pinfunction "2_2") (pintype "passive"))
      (node (ref "R2") (pin "2") (pinfunction "2_2") (pintype "passive"))
    )
    (net (code "72") (name "Net-(Q1-B)") (class "Default")
      (node (ref "Q1") (pin "1") (pinfunction "B_1") (pintype "passive"))
      (node (ref "R5") (pin "2") (pinfunction "2_2") (pintype "passive"))
      (node (ref "R6") (pin "1") (pinfunction "1_1") (pintype "passive"))
    )
    (net (code "73") (name "Net-(Q1-C)") (class "Default")
      (node (ref "Q1") (pin "3") (pinfunction "C_3") (pintype "passive"))
      (node (ref "R7") (pin "2") (pinfunction "2_2") (pintype "passive"))
    )
    (net (code "74") (name "Net-(U1-RCC_OSC_IN{slash}PH0)") (class "Default")
      (node (ref "C1") (pin "1") (pinfunction "1_1") (pintype "passive"))
      (node (ref "U1") (pin "5") (pinfunction "RCC_OSC_IN/PH0_5") (pintype "passive"))
      (node (ref "X1") (pin "3") (pinfunction "3_3") (pintype "passive"))
    )
    (net (code "75") (name "Net-(U1-RCC_OSC_OUT{slash}PH1)") (class "Default")
      (node (ref "C2") (pin "1") (pinfunction "1_1") (pintype "passive"))
      (node (ref "U1") (pin "6") (pinfunction "RCC_OSC_OUT/PH1_6") (pintype "passive"))
      (node (ref "X1") (pin "1") (pinfunction "1_1") (pintype "passive"))
    )
    (net (code "76") (name "Net-(U1-VCAP_1)") (class "Default")
      (node (ref "C13") (pin "2") (pinfunction "2_2") (pintype "passive"))
      (node (ref "U1") (pin "31") (pinfunction "VCAP_1_31") (pintype "passive"))
    )
    (net (code "77") (name "Net-(U1-VCAP_2)") (class "Default")
      (node (ref "C14") (pin "2") (pinfunction "2_2") (pintype "passive"))
      (node (ref "U1") (pin "47") (pinfunction "VCAP_2_47") (pintype "passive"))
    )
    (net (code "78") (name "Net-(U4-BAT)") (class "Default")
      (node (ref "C30") (pin "2") (pinfunction "2_2") (pintype "passive"))
      (node (ref "R13") (pin "1") (pinfunction "1_1") (pintype "passive"))
      (node (ref "U4") (pin "6") (pinfunction "BAT_6") (pintype "passive"))
    )
    (net (code "79") (name "Net-(U4-SW)") (class "Default")
      (node (ref "L1") (pin "1") (pinfunction "1_1") (pintype "passive"))
      (node (ref "U4") (pin "7") (pinfunction "SW_7") (pintype "passive"))
    )
    (net (code "80") (name "USBVCC") (class "Default")
      (node (ref "C26") (pin "1") (pinfunction "1_1") (pintype "passive"))
      (node (ref "C27") (pin "1") (pinfunction "1_1") (pintype "passive"))
      (node (ref "R14") (pin "1") (pinfunction "1_1") (pintype "passive"))
      (node (ref "U4") (pin "1") (pinfunction "VIN_1") (pintype "passive"))
      (node (ref "USB1") (pin "A4") (pinfunction "VBUS_A4") (pintype "passive"))
      (node (ref "USB1") (pin "A9") (pinfunction "VBUS_A9") (pintype "passive"))
      (node (ref "USB1") (pin "B4") (pinfunction "VBUS_B4") (pintype "passive"))
      (node (ref "USB1") (pin "B9") (pinfunction "VBUS_B9") (pintype "passive"))
    )
    (net (code "81") (name "VCC5V") (class "Default")
      (node (ref "C15") (pin "1") (pinfunction "1_1") (pintype "passive"))
      (node (ref "C16") (pin "1") (pinfunction "1_1") (pintype "passive"))
      (node (ref "C22") (pin "1") (pinfunction "1_1") (pintype "passive"))
      (node (ref "C23") (pin "1") (pinfunction "1_1") (pintype "passive"))
      (node (ref "C28") (pin "1") (pinfunction "1_1") (pintype "passive"))
      (node (ref "C29") (pin "1") (pinfunction "1_1") (pintype "passive"))
      (node (ref "P4") (pin "1") (pinfunction "1_1") (pintype "passive"))
      (node (ref "P5") (pin "1") (pinfunction "1_1") (pintype "passive"))
      (node (ref "R14") (pin "2") (pinfunction "2_2") (pintype "passive"))
      (node (ref "U2") (pin "1") (pinfunction "EN_1") (pintype "passive"))
      (node (ref "U2") (pin "3") (pinfunction "EN_3") (pintype "passive"))
      (node (ref "U3") (pin "1") (pinfunction "EN_1") (pintype "passive"))
      (node (ref "U3") (pin "3") (pinfunction "EN_3") (pintype "passive"))
      (node (ref "U4") (pin "8") (pinfunction "VOUT_8") (pintype "passive"))
    )
    (net (code "82") (name "VCC_LCD") (class "Default")
      (node (ref "1") (pin "39") (pinfunction "39_39") (pintype "passive"))
      (node (ref "C24") (pin "1") (pinfunction "1_1") (pintype "passive"))
      (node (ref "C25") (pin "1") (pinfunction "1_1") (pintype "passive"))
      (node (ref "P2") (pin "1") (pinfunction "1_1") (pintype "passive"))
      (node (ref "P2") (pin "3") (pinfunction "3_3") (pintype "passive"))
      (node (ref "Q1") (pin "2") (pinfunction "E_2") (pintype "passive"))
      (node (ref "R6") (pin "2") (pinfunction "2_2") (pintype "passive"))
      (node (ref "TP2") (pin "1") (pinfunction "1_1") (pintype "passive"))
      (node (ref "U3") (pin "5") (pinfunction "VOUT_5") (pintype "passive"))
    )
    (net (code "83") (name "unconnected-(P1-PadMP1)") (class "Default")
      (node (ref "P1") (pin "MP1") (pinfunction "MP1_MP1") (pintype "passive+no_connect"))
    )
    (net (code "84") (name "unconnected-(P1-PadMP2)") (class "Default")
      (node (ref "P1") (pin "MP2") (pinfunction "MP2_MP2") (pintype "passive+no_connect"))
    )
    (net (code "85") (name "unconnected-(P2-PadMP1)") (class "Default")
      (node (ref "P2") (pin "MP1") (pinfunction "MP1_MP1") (pintype "passive+no_connect"))
    )
    (net (code "86") (name "unconnected-(P2-PadMP2)") (class "Default")
      (node (ref "P2") (pin "MP2") (pinfunction "MP2_MP2") (pintype "passive+no_connect"))
    )
    (net (code "87") (name "unconnected-(P3-PadMP1)") (class "Default")
      (node (ref "P3") (pin "MP1") (pinfunction "MP1_MP1") (pintype "passive+no_connect"))
    )
    (net (code "88") (name "unconnected-(P3-PadMP2)") (class "Default")
      (node (ref "P3") (pin "MP2") (pinfunction "MP2_MP2") (pintype "passive+no_connect"))
    )
    (net (code "89") (name "unconnected-(P4-PadMP1)") (class "Default")
      (node (ref "P4") (pin "MP1") (pinfunction "MP1_MP1") (pintype "passive+no_connect"))
    )
    (net (code "90") (name "unconnected-(P4-PadMP2)") (class "Default")
      (node (ref "P4") (pin "MP2") (pinfunction "MP2_MP2") (pintype "passive+no_connect"))
    )
    (net (code "91") (name "unconnected-(P5-PadMP1)") (class "Default")
      (node (ref "P5") (pin "MP1") (pinfunction "MP1_MP1") (pintype "passive+no_connect"))
    )
    (net (code "92") (name "unconnected-(P5-PadMP2)") (class "Default")
      (node (ref "P5") (pin "MP2") (pinfunction "MP2_MP2") (pintype "passive+no_connect"))
    )
    (net (code "93") (name "unconnected-(U1-PA15-Pad50)") (class "Default")
      (node (ref "U1") (pin "50") (pinfunction "PA15_50") (pintype "passive+no_connect"))
    )
    (net (code "94") (name "unconnected-(U1-PB2{slash}BOOT1-Pad28)") (class "Default")
      (node (ref "U1") (pin "28") (pinfunction "PB2/BOOT1_28") (pintype "passive+no_connect"))
    )
    (net (code "95") (name "unconnected-(U2-NC-Pad4)") (class "Default")
      (node (ref "U2") (pin "4") (pinfunction "NC_4") (pintype "passive+no_connect"))
    )
    (net (code "96") (name "unconnected-(U3-NC-Pad4)") (class "Default")
      (node (ref "U3") (pin "4") (pinfunction "NC_4") (pintype "passive+no_connect"))
    )
    (net (code "97") (name "unconnected-(USB1-CC1-PadA5)") (class "Default")
      (node (ref "USB1") (pin "A5") (pinfunction "CC1_A5") (pintype "passive+no_connect"))
    )
    (net (code "98") (name "unconnected-(USB1-CC2-PadB5)") (class "Default")
      (node (ref "USB1") (pin "B5") (pinfunction "CC2_B5") (pintype "passive+no_connect"))
    )
    (net (code "99") (name "unconnected-(USB1-RX1+-PadB11)") (class "Default")
      (node (ref "USB1") (pin "B11") (pinfunction "RX1+_B11") (pintype "passive+no_connect"))
    )
    (net (code "100") (name "unconnected-(USB1-RX1--PadB10)") (class "Default")
      (node (ref "USB1") (pin "B10") (pinfunction "RX1-_B10") (pintype "passive+no_connect"))
    )
    (net (code "101") (name "unconnected-(USB1-RX2+-PadA11)") (class "Default")
      (node (ref "USB1") (pin "A11") (pinfunction "RX2+_A11") (pintype "passive+no_connect"))
    )
    (net (code "102") (name "unconnected-(USB1-RX2--PadA10)") (class "Default")
      (node (ref "USB1") (pin "A10") (pinfunction "RX2-_A10") (pintype "passive+no_connect"))
    )
    (net (code "103") (name "unconnected-(USB1-SBU1-PadA8)") (class "Default")
      (node (ref "USB1") (pin "A8") (pinfunction "SBU1_A8") (pintype "passive+no_connect"))
    )
    (net (code "104") (name "unconnected-(USB1-SBU2-PadB8)") (class "Default")
      (node (ref "USB1") (pin "B8") (pinfunction "SBU2_B8") (pintype "passive+no_connect"))
    )
    (net (code "105") (name "unconnected-(USB1-SH1-Pad1)") (class "Default")
      (node (ref "USB1") (pin "1") (pinfunction "SH1_1") (pintype "passive+no_connect"))
    )
    (net (code "106") (name "unconnected-(USB1-SH2-Pad2)") (class "Default")
      (node (ref "USB1") (pin "2") (pinfunction "SH2_2") (pintype "passive+no_connect"))
    )
    (net (code "107") (name "unconnected-(USB1-SH3-Pad3)") (class "Default")
      (node (ref "USB1") (pin "3") (pinfunction "SH3_3") (pintype "passive+no_connect"))
    )
    (net (code "108") (name "unconnected-(USB1-SH4-Pad4)") (class "Default")
      (node (ref "USB1") (pin "4") (pinfunction "SH4_4") (pintype "passive+no_connect"))
    )
    (net (code "109") (name "unconnected-(USB1-TX1+-PadA2)") (class "Default")
      (node (ref "USB1") (pin "A2") (pinfunction "TX1+_A2") (pintype "passive+no_connect"))
    )
    (net (code "110") (name "unconnected-(USB1-TX1--PadA3)") (class "Default")
      (node (ref "USB1") (pin "A3") (pinfunction "TX1-_A3") (pintype "passive+no_connect"))
    )
    (net (code "111") (name "unconnected-(USB1-TX2+-PadB2)") (class "Default")
      (node (ref "USB1") (pin "B2") (pinfunction "TX2+_B2") (pintype "passive+no_connect"))
    )
    (net (code "112") (name "unconnected-(USB1-TX2--PadB3)") (class "Default")
      (node (ref "USB1") (pin "B3") (pinfunction "TX2-_B3") (pintype "passive+no_connect"))
    )
  )
)
